# PROC106B_HD_CONN_PWR_SW.net
KiCad netlist of a schematic drawn in Altium Designer
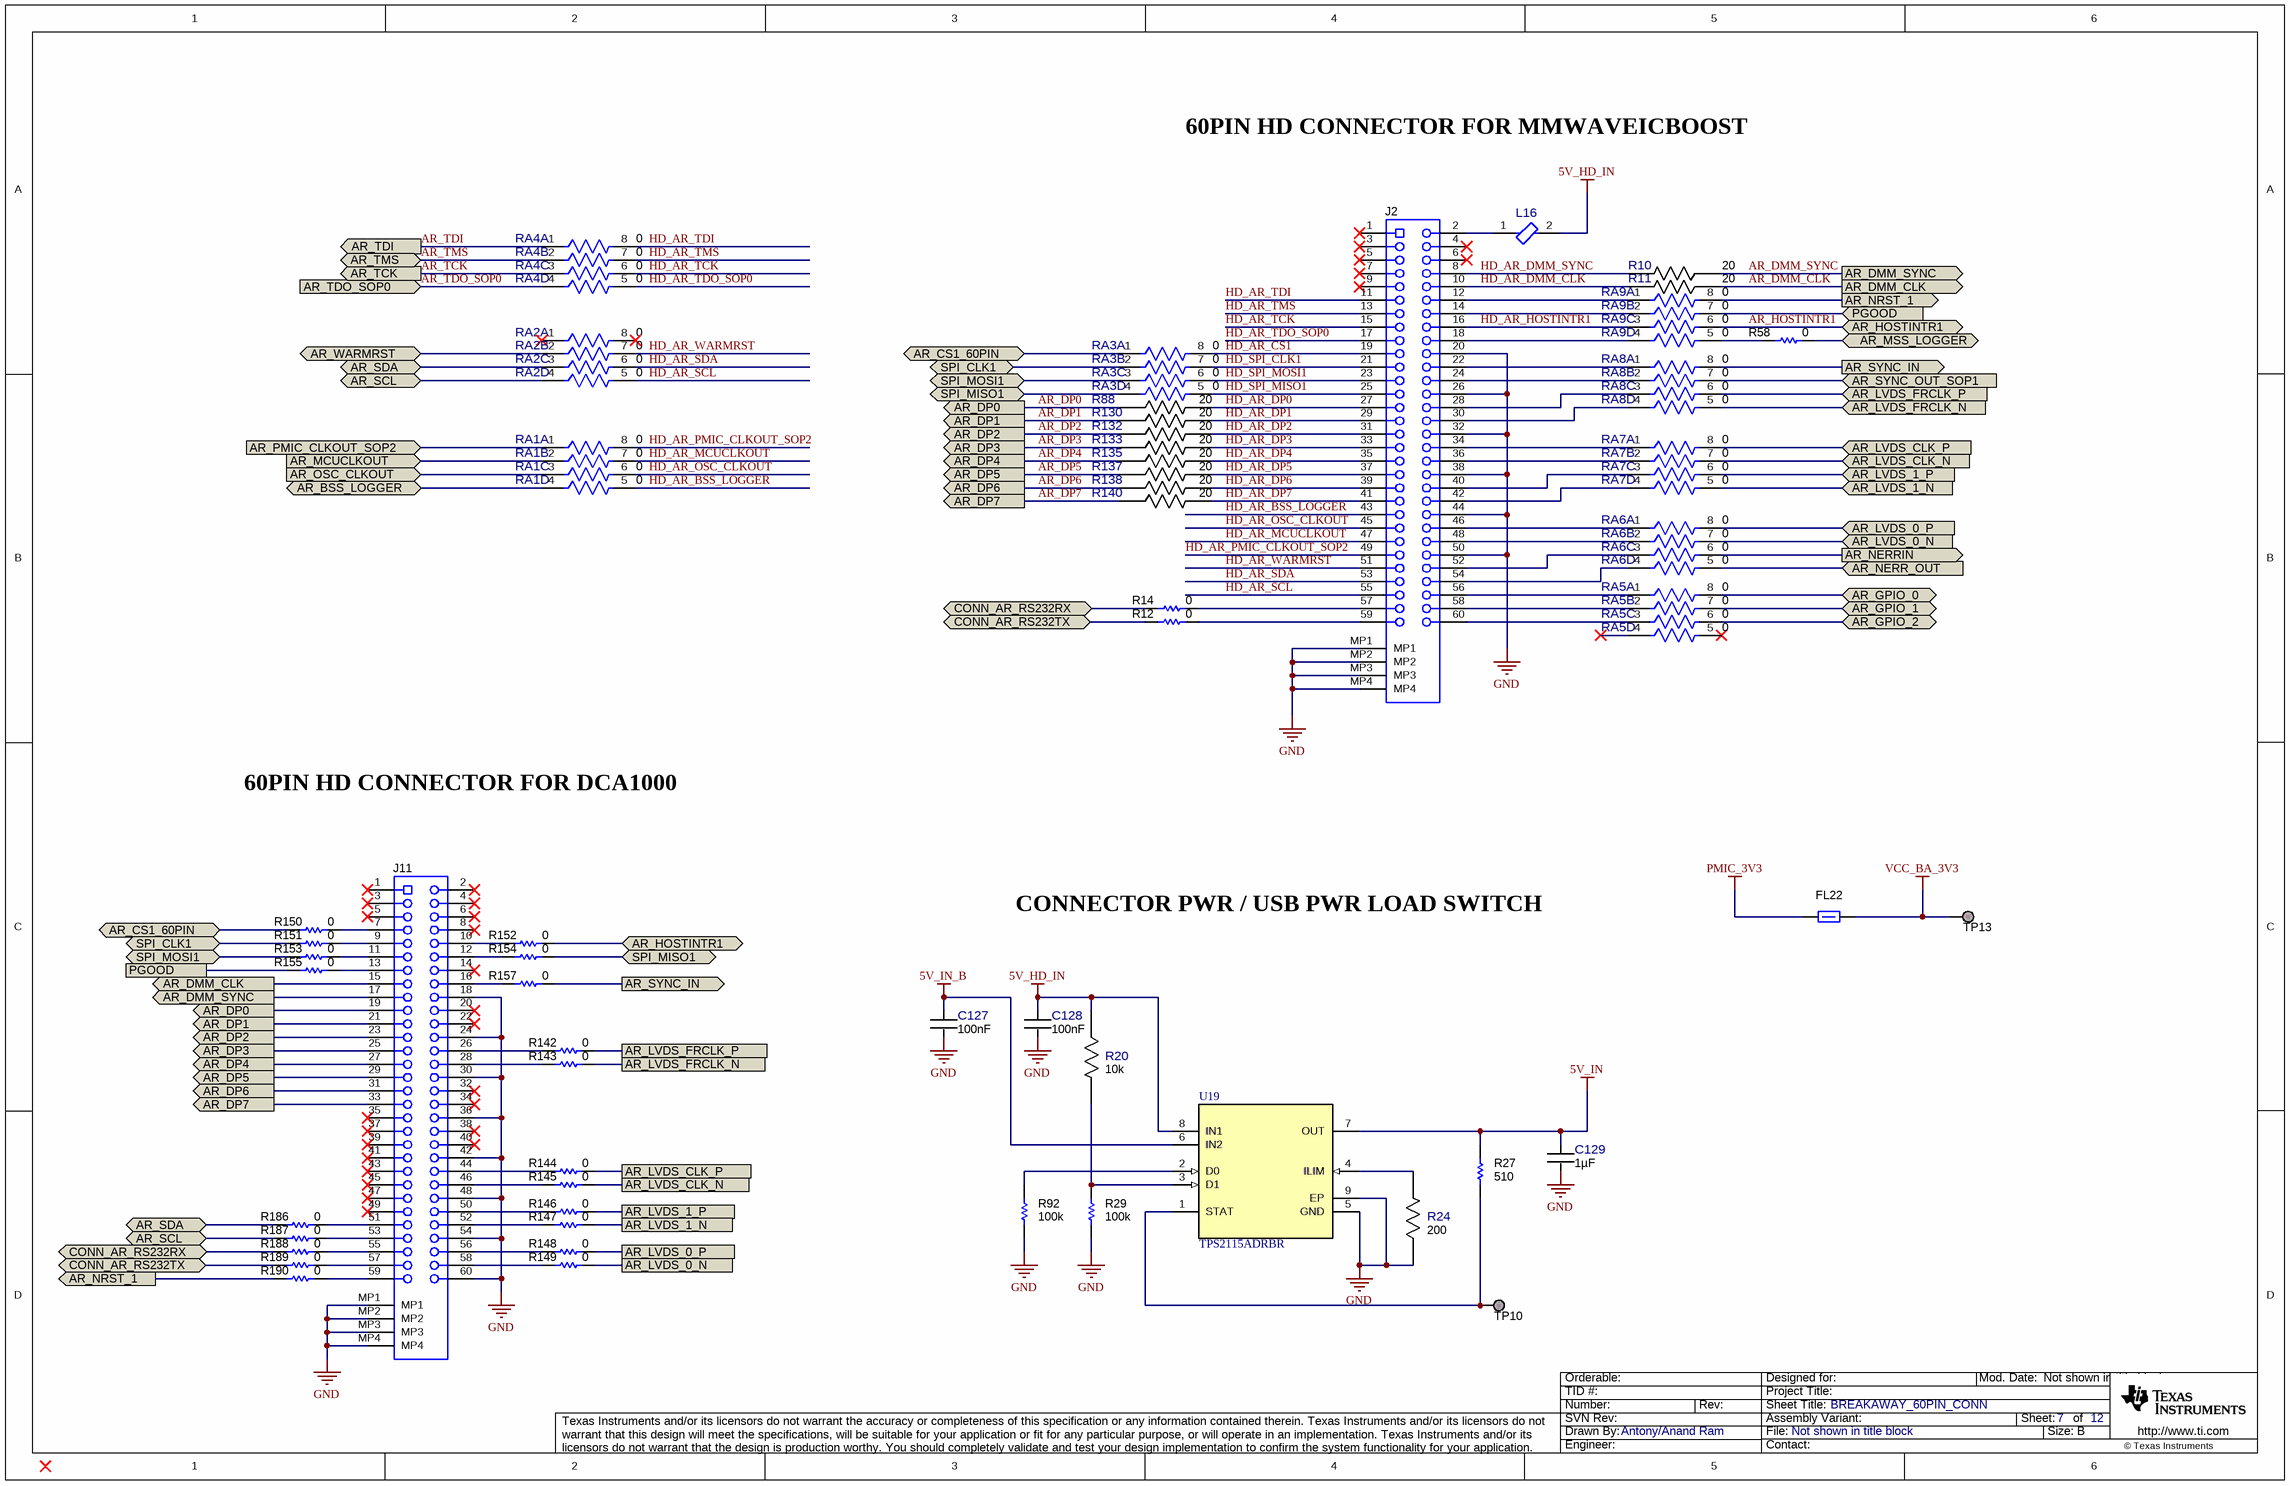
[diagram p0: PROC106B_HD_CONN_PWR_SW.SchDoc]

(export (version "E")
  (design (tool "Eeschema 10.0.6"))
  (components
    (comp (ref "C127")
      (value "GRM033R6YA104KE14D")
      (footprint "FP-GRM033R6YA104KE14D_0201 (0603 Metric)-IPC_C")
      (description "Cap Ceramic 0.1uF 35V X5R 10% Pad SMD 0201 85C T/R")
      (fields (field (name "CAP_F") "100nF") (field (name "MANUFACTURER") "Murata Electronics North America"))
      (libsource (lib "Altium Vault - TI") (part "SYM-B32642B0223J"))
    )
    (comp (ref "C128")
      (value "GRM033R6YA104KE14D")
      (footprint "FP-GRM033R6YA104KE14D_0201 (0603 Metric)-IPC_C")
      (description "Cap Ceramic 0.1uF 35V X5R 10% Pad SMD 0201 85C T/R")
      (fields (field (name "CAP_F") "100nF") (field (name "MANUFACTURER") "Murata Electronics North America"))
      (libsource (lib "Altium Vault - TI") (part "SYM-B32642B0223J"))
    )
    (comp (ref "C129")
      (value "CL03A105MO3NRNH")
      (footprint "FP-CL03A105MO3NRNH_0201-IPC_C")
      (description "1µF ±20% 16V Ceramic Capacitor X5R 0201")
      (fields (field (name "CAP_F") "1µF") (field (name "MANUFACTURER") "Samsung Electro-Mechanics"))
      (libsource (lib "Altium Vault - TI") (part "SYM-B32642B0223J"))
    )
    (comp (ref "FL22")
      (value "BLM15PD300SZ1D")
      (footprint "0402L")
      (description "Inductor, Ferrite Bead, Ferrite, 2.2 A, 0.035 ohm, AEC-Q200 Grade 1, SMD")
      (fields (field (name "MANUFACTURER") "MuRata") (field (name "PUBLISHER") "Texas Instruments"))
      (libsource (lib "Altium Vault - TI") (part "Ferrite_Bead"))
    )
    (comp (ref "J2")
      (value "QSH-030-01-L-D-A")
      (footprint "Samtec_QSH-030-01-X-D-A")
      (description "Receptacle, 0.5 mm, 30x2, Gold, TH")
      (fields (field (name "MANUFACTURER") "Samtec") (field (name "PUBLISHER") "Texas Instruments"))
      (libsource (lib "Altium Vault - TI") (part "Receptacle_30x2_4MP_LeftRight"))
    )
    (comp (ref "J11")
      (value "QSH-030-01-L-D-A")
      (footprint "Samtec_QSH-030-01-X-D-A")
      (description "Receptacle, 0.5 mm, 30x2, Gold, TH")
      (fields (field (name "MANUFACTURER") "Samtec") (field (name "PUBLISHER") "Texas Instruments"))
      (libsource (lib "Altium Vault - TI") (part "CMP-0075524-1"))
    )
    (comp (ref "L16")
      (value "MPZ2012S101ATD25")
      (footprint "FP-MPZ2012S101ATD25_0805-MFG")
      (description "100 Ohms @ 100MHz 1 Power Line Ferrite Bead 0805 (2012 Metric) 4A 20mOhm")
      (fields (field (name "MANUFACTURER") "TDK") (field (name "DIGIKEY PART NUMBER") "445-172903-1-ND"))
      (libsource (lib "Altium Vault - TI") (part "SYM-MPZ2012S101ATD25"))
    )
    (comp (ref "R10")
      (value "AC0201FR-0720RL")
      (footprint "FP-AC0201FR-0720RL_0201-IPC_C")
      (description "RES SMD 20 OHM 1% 1/20W 0201")
      (fields (field (name "MANUFACTURER") "Yageo") (field (name "RES_OHM") "20"))
      (libsource (lib "Altium Vault - TI") (part "SYM-PMR18EZPJ000"))
    )
    (comp (ref "R11")
      (value "AC0201FR-0720RL")
      (footprint "FP-AC0201FR-0720RL_0201-IPC_C")
      (description "RES SMD 20 OHM 1% 1/20W 0201")
      (fields (field (name "MANUFACTURER") "Yageo") (field (name "RES_OHM") "20"))
      (libsource (lib "Altium Vault - TI") (part "SYM-PMR18EZPJ000"))
    )
    (comp (ref "R12")
      (value "RC0201JR-070RL")
      (footprint "FP-RC0201JR-070RL_0201 (0603 Metric)-MFG")
      (description "RES SMD 0 OHM JUMPER 1/20W 0201")
      (fields (field (name "MANUFACTURER") "Yageo") (field (name "RES_OHM") "0"))
      (libsource (lib "Altium Vault - TI") (part "SYM-WSR3R1500F"))
    )
    (comp (ref "R14")
      (value "RC0201JR-070RL")
      (footprint "FP-RC0201JR-070RL_0201 (0603 Metric)-MFG")
      (description "RES SMD 0 OHM JUMPER 1/20W 0201")
      (fields (field (name "MANUFACTURER") "Yageo") (field (name "RES_OHM") "0"))
      (libsource (lib "Altium Vault - TI") (part "SYM-WSR3R1500F"))
    )
    (comp (ref "R20")
      (value "RR0306P-103-D")
      (footprint "FP-RR0306P-103-D_0201-IPC_C")
      (description "10 kOhms ±0.5% 0.05W, 1/20W Chip Resistor 0201 (0603 Metric)  Thin Film")
      (fields (field (name "MANUFACTURER") "Susumu") (field (name "RES_OHM") "10k"))
      (libsource (lib "Altium Vault - TI") (part "SYM-PMR18EZPJ000"))
    )
    (comp (ref "R24")
      (value "CRCW0402200RFKEDHP")
      (footprint "FP-CRCW0402200RFKEDHP_0402-IPC_C")
      (description "RES SMD 200 OHM 1% 1/5W 0402")
      (fields (field (name "MANUFACTURER") "Vishay Dale") (field (name "RES_OHM") "200"))
      (libsource (lib "Altium Vault - TI") (part "SYM-PMR18EZPJ000"))
    )
    (comp (ref "R27")
      (value "510")
      (footprint "0201L")
      (description "RES, 510, 5%, 0.05 W, 0201")
      (fields
        (field (name "MANUFACTURER") "Yageo America")
        (field (name "PARTNUMBER") "RC0201JR-07510RL")
        (field (name "PUBLISHER") "Texas Instruments")
      )
      (libsource (lib "Altium Vault - TI") (part "Resistor"))
    )
    (comp (ref "R29")
      (value "100k")
      (footprint "0201L")
      (description "RES, 100 k, 1%, 0.05 W, 0201")
      (fields (field (name "MANUFACTURER") "Vishay-Dale") (field (name "PARTNUMBER") "CRCW0201100KFKED"))
      (libsource (lib "Altium Vault - TI") (part "Resistor"))
    )
    (comp (ref "R58")
      (value "RC0201JR-070RL")
      (footprint "FP-RC0201JR-070RL_0201 (0603 Metric)-MFG")
      (description "RES SMD 0 OHM JUMPER 1/20W 0201")
      (fields (field (name "MANUFACTURER") "Yageo") (field (name "RES_OHM") "0"))
      (libsource (lib "Altium Vault - TI") (part "SYM-WSR3R1500F"))
    )
    (comp (ref "R88")
      (value "AC0201FR-0720RL")
      (footprint "FP-AC0201FR-0720RL_0201-IPC_C")
      (description "RES SMD 20 OHM 1% 1/20W 0201")
      (fields (field (name "MANUFACTURER") "Yageo") (field (name "RES_OHM") "20"))
      (libsource (lib "Altium Vault - TI") (part "SYM-PMR18EZPJ000"))
    )
    (comp (ref "R92")
      (value "100k")
      (footprint "0201L")
      (description "RES, 100 k, 1%, 0.05 W, 0201")
      (fields (field (name "MANUFACTURER") "Vishay-Dale") (field (name "PARTNUMBER") "CRCW0201100KFKED"))
      (libsource (lib "Altium Vault - TI") (part "Resistor"))
    )
    (comp (ref "R130")
      (value "AC0201FR-0720RL")
      (footprint "FP-AC0201FR-0720RL_0201-IPC_C")
      (description "RES SMD 20 OHM 1% 1/20W 0201")
      (fields (field (name "MANUFACTURER") "Yageo") (field (name "RES_OHM") "20"))
      (libsource (lib "Altium Vault - TI") (part "SYM-PMR18EZPJ000"))
    )
    (comp (ref "R132")
      (value "AC0201FR-0720RL")
      (footprint "FP-AC0201FR-0720RL_0201-IPC_C")
      (description "RES SMD 20 OHM 1% 1/20W 0201")
      (fields (field (name "MANUFACTURER") "Yageo") (field (name "RES_OHM") "20"))
      (libsource (lib "Altium Vault - TI") (part "SYM-PMR18EZPJ000"))
    )
    (comp (ref "R133")
      (value "AC0201FR-0720RL")
      (footprint "FP-AC0201FR-0720RL_0201-IPC_C")
      (description "RES SMD 20 OHM 1% 1/20W 0201")
      (fields (field (name "MANUFACTURER") "Yageo") (field (name "RES_OHM") "20"))
      (libsource (lib "Altium Vault - TI") (part "SYM-PMR18EZPJ000"))
    )
    (comp (ref "R135")
      (value "AC0201FR-0720RL")
      (footprint "FP-AC0201FR-0720RL_0201-IPC_C")
      (description "RES SMD 20 OHM 1% 1/20W 0201")
      (fields (field (name "MANUFACTURER") "Yageo") (field (name "RES_OHM") "20"))
      (libsource (lib "Altium Vault - TI") (part "SYM-PMR18EZPJ000"))
    )
    (comp (ref "R137")
      (value "AC0201FR-0720RL")
      (footprint "FP-AC0201FR-0720RL_0201-IPC_C")
      (description "RES SMD 20 OHM 1% 1/20W 0201")
      (fields (field (name "MANUFACTURER") "Yageo") (field (name "RES_OHM") "20"))
      (libsource (lib "Altium Vault - TI") (part "SYM-PMR18EZPJ000"))
    )
    (comp (ref "R138")
      (value "AC0201FR-0720RL")
      (footprint "FP-AC0201FR-0720RL_0201-IPC_C")
      (description "RES SMD 20 OHM 1% 1/20W 0201")
      (fields (field (name "MANUFACTURER") "Yageo") (field (name "RES_OHM") "20"))
      (libsource (lib "Altium Vault - TI") (part "SYM-PMR18EZPJ000"))
    )
    (comp (ref "R140")
      (value "AC0201FR-0720RL")
      (footprint "FP-AC0201FR-0720RL_0201-IPC_C")
      (description "RES SMD 20 OHM 1% 1/20W 0201")
      (fields (field (name "MANUFACTURER") "Yageo") (field (name "RES_OHM") "20"))
      (libsource (lib "Altium Vault - TI") (part "SYM-PMR18EZPJ000"))
    )
    (comp (ref "R142")
      (value "RC0201JR-070RL")
      (footprint "FP-RC0201JR-070RL_0201 (0603 Metric)-MFG")
      (description "RES SMD 0 OHM JUMPER 1/20W 0201")
      (fields (field (name "MANUFACTURER") "Yageo") (field (name "RES_OHM") "0"))
      (libsource (lib "Altium Vault - TI") (part "SYM-WSR3R1500F"))
    )
    (comp (ref "R143")
      (value "RC0201JR-070RL")
      (footprint "FP-RC0201JR-070RL_0201 (0603 Metric)-MFG")
      (description "RES SMD 0 OHM JUMPER 1/20W 0201")
      (fields (field (name "MANUFACTURER") "Yageo") (field (name "RES_OHM") "0"))
      (libsource (lib "Altium Vault - TI") (part "SYM-WSR3R1500F"))
    )
    (comp (ref "R144")
      (value "RC0201JR-070RL")
      (footprint "FP-RC0201JR-070RL_0201 (0603 Metric)-MFG")
      (description "RES SMD 0 OHM JUMPER 1/20W 0201")
      (fields (field (name "MANUFACTURER") "Yageo") (field (name "RES_OHM") "0"))
      (libsource (lib "Altium Vault - TI") (part "SYM-WSR3R1500F"))
    )
    (comp (ref "R145")
      (value "RC0201JR-070RL")
      (footprint "FP-RC0201JR-070RL_0201 (0603 Metric)-MFG")
      (description "RES SMD 0 OHM JUMPER 1/20W 0201")
      (fields (field (name "MANUFACTURER") "Yageo") (field (name "RES_OHM") "0"))
      (libsource (lib "Altium Vault - TI") (part "SYM-WSR3R1500F"))
    )
    (comp (ref "R146")
      (value "RC0201JR-070RL")
      (footprint "FP-RC0201JR-070RL_0201 (0603 Metric)-MFG")
      (description "RES SMD 0 OHM JUMPER 1/20W 0201")
      (fields (field (name "MANUFACTURER") "Yageo") (field (name "RES_OHM") "0"))
      (libsource (lib "Altium Vault - TI") (part "SYM-WSR3R1500F"))
    )
    (comp (ref "R147")
      (value "RC0201JR-070RL")
      (footprint "FP-RC0201JR-070RL_0201 (0603 Metric)-MFG")
      (description "RES SMD 0 OHM JUMPER 1/20W 0201")
      (fields (field (name "MANUFACTURER") "Yageo") (field (name "RES_OHM") "0"))
      (libsource (lib "Altium Vault - TI") (part "SYM-WSR3R1500F"))
    )
    (comp (ref "R148")
      (value "RC0201JR-070RL")
      (footprint "FP-RC0201JR-070RL_0201 (0603 Metric)-MFG")
      (description "RES SMD 0 OHM JUMPER 1/20W 0201")
      (fields (field (name "MANUFACTURER") "Yageo") (field (name "RES_OHM") "0"))
      (libsource (lib "Altium Vault - TI") (part "SYM-WSR3R1500F"))
    )
    (comp (ref "R149")
      (value "RC0201JR-070RL")
      (footprint "FP-RC0201JR-070RL_0201 (0603 Metric)-MFG")
      (description "RES SMD 0 OHM JUMPER 1/20W 0201")
      (fields (field (name "MANUFACTURER") "Yageo") (field (name "RES_OHM") "0"))
      (libsource (lib "Altium Vault - TI") (part "SYM-WSR3R1500F"))
    )
    (comp (ref "R150")
      (value "RC0201JR-070RL")
      (footprint "FP-RC0201JR-070RL_0201 (0603 Metric)-MFG")
      (description "RES SMD 0 OHM JUMPER 1/20W 0201")
      (fields (field (name "MANUFACTURER") "Yageo") (field (name "RES_OHM") "0"))
      (libsource (lib "Altium Vault - TI") (part "SYM-WSR3R1500F"))
    )
    (comp (ref "R151")
      (value "RC0201JR-070RL")
      (footprint "FP-RC0201JR-070RL_0201 (0603 Metric)-MFG")
      (description "RES SMD 0 OHM JUMPER 1/20W 0201")
      (fields (field (name "MANUFACTURER") "Yageo") (field (name "RES_OHM") "0"))
      (libsource (lib "Altium Vault - TI") (part "SYM-WSR3R1500F"))
    )
    (comp (ref "R152")
      (value "RC0201JR-070RL")
      (footprint "FP-RC0201JR-070RL_0201 (0603 Metric)-MFG")
      (description "RES SMD 0 OHM JUMPER 1/20W 0201")
      (fields (field (name "MANUFACTURER") "Yageo") (field (name "RES_OHM") "0"))
      (libsource (lib "Altium Vault - TI") (part "SYM-WSR3R1500F"))
    )
    (comp (ref "R153")
      (value "RC0201JR-070RL")
      (footprint "FP-RC0201JR-070RL_0201 (0603 Metric)-MFG")
      (description "RES SMD 0 OHM JUMPER 1/20W 0201")
      (fields (field (name "MANUFACTURER") "Yageo") (field (name "RES_OHM") "0"))
      (libsource (lib "Altium Vault - TI") (part "SYM-WSR3R1500F"))
    )
    (comp (ref "R154")
      (value "RC0201JR-070RL")
      (footprint "FP-RC0201JR-070RL_0201 (0603 Metric)-MFG")
      (description "RES SMD 0 OHM JUMPER 1/20W 0201")
      (fields (field (name "MANUFACTURER") "Yageo") (field (name "RES_OHM") "0"))
      (libsource (lib "Altium Vault - TI") (part "SYM-WSR3R1500F"))
    )
    (comp (ref "R155")
      (value "RC0201JR-070RL")
      (footprint "FP-RC0201JR-070RL_0201 (0603 Metric)-MFG")
      (description "RES SMD 0 OHM JUMPER 1/20W 0201")
      (fields (field (name "MANUFACTURER") "Yageo") (field (name "RES_OHM") "0"))
      (libsource (lib "Altium Vault - TI") (part "SYM-WSR3R1500F"))
    )
    (comp (ref "R157")
      (value "RC0201JR-070RL")
      (footprint "FP-RC0201JR-070RL_0201 (0603 Metric)-MFG")
      (description "RES SMD 0 OHM JUMPER 1/20W 0201")
      (fields (field (name "MANUFACTURER") "Yageo") (field (name "RES_OHM") "0"))
      (libsource (lib "Altium Vault - TI") (part "SYM-WSR3R1500F"))
    )
    (comp (ref "R186")
      (value "RC0201JR-070RL")
      (footprint "FP-RC0201JR-070RL_0201 (0603 Metric)-MFG")
      (description "RES SMD 0 OHM JUMPER 1/20W 0201")
      (fields (field (name "MANUFACTURER") "Yageo") (field (name "RES_OHM") "0"))
      (libsource (lib "Altium Vault - TI") (part "SYM-WSR3R1500F"))
    )
    (comp (ref "R187")
      (value "RC0201JR-070RL")
      (footprint "FP-RC0201JR-070RL_0201 (0603 Metric)-MFG")
      (description "RES SMD 0 OHM JUMPER 1/20W 0201")
      (fields (field (name "MANUFACTURER") "Yageo") (field (name "RES_OHM") "0"))
      (libsource (lib "Altium Vault - TI") (part "SYM-WSR3R1500F"))
    )
    (comp (ref "R188")
      (value "RC0201JR-070RL")
      (footprint "FP-RC0201JR-070RL_0201 (0603 Metric)-MFG")
      (description "RES SMD 0 OHM JUMPER 1/20W 0201")
      (fields (field (name "MANUFACTURER") "Yageo") (field (name "RES_OHM") "0"))
      (libsource (lib "Altium Vault - TI") (part "SYM-WSR3R1500F"))
    )
    (comp (ref "R189")
      (value "RC0201JR-070RL")
      (footprint "FP-RC0201JR-070RL_0201 (0603 Metric)-MFG")
      (description "RES SMD 0 OHM JUMPER 1/20W 0201")
      (fields (field (name "MANUFACTURER") "Yageo") (field (name "RES_OHM") "0"))
      (libsource (lib "Altium Vault - TI") (part "SYM-WSR3R1500F"))
    )
    (comp (ref "R190")
      (value "RC0201JR-070RL")
      (footprint "FP-RC0201JR-070RL_0201 (0603 Metric)-MFG")
      (description "RES SMD 0 OHM JUMPER 1/20W 0201")
      (fields (field (name "MANUFACTURER") "Yageo") (field (name "RES_OHM") "0"))
      (libsource (lib "Altium Vault - TI") (part "SYM-WSR3R1500F"))
    )
    (comp (ref "RA1")
      (value "EXB-18VR000X")
      (footprint "FP-EXB-18VR000X_0502-MFG")
      (description "RES ARRAY 4 RES ZERO OHM 0502")
      (fields (field (name "MANUFACTURER") "Panasonic Electronic Components") (field (name "RES_OHM") "0"))
      (libsource (lib "Altium Vault - TI") (part "SYM-EXB-18VR000X"))
    )
    (comp (ref "RA2")
      (value "EXB-18VR000X")
      (footprint "FP-EXB-18VR000X_0502-MFG")
      (description "RES ARRAY 4 RES ZERO OHM 0502")
      (fields (field (name "MANUFACTURER") "Panasonic Electronic Components") (field (name "RES_OHM") "0"))
      (libsource (lib "Altium Vault - TI") (part "SYM-EXB-18VR000X"))
    )
    (comp (ref "RA3")
      (value "EXB-18VR000X")
      (footprint "FP-EXB-18VR000X_0502-MFG")
      (description "RES ARRAY 4 RES ZERO OHM 0502")
      (fields (field (name "MANUFACTURER") "Panasonic Electronic Components") (field (name "RES_OHM") "0"))
      (libsource (lib "Altium Vault - TI") (part "SYM-EXB-18VR000X"))
    )
    (comp (ref "RA4")
      (value "EXB-18VR000X")
      (footprint "FP-EXB-18VR000X_0502-MFG")
      (description "RES ARRAY 4 RES ZERO OHM 0502")
      (fields (field (name "MANUFACTURER") "Panasonic Electronic Components") (field (name "RES_OHM") "0"))
      (libsource (lib "Altium Vault - TI") (part "SYM-EXB-18VR000X"))
    )
    (comp (ref "RA5")
      (value "EXB-18VR000X")
      (footprint "FP-EXB-18VR000X_0502-MFG")
      (description "RES ARRAY 4 RES ZERO OHM 0502")
      (fields (field (name "MANUFACTURER") "Panasonic Electronic Components") (field (name "RES_OHM") "0"))
      (libsource (lib "Altium Vault - TI") (part "SYM-EXB-18VR000X"))
    )
    (comp (ref "RA6")
      (value "EXB-18VR000X")
      (footprint "FP-EXB-18VR000X_0502-MFG")
      (description "RES ARRAY 4 RES ZERO OHM 0502")
      (fields (field (name "MANUFACTURER") "Panasonic Electronic Components") (field (name "RES_OHM") "0"))
      (libsource (lib "Altium Vault - TI") (part "SYM-EXB-18VR000X"))
    )
    (comp (ref "RA7")
      (value "EXB-18VR000X")
      (footprint "FP-EXB-18VR000X_0502-MFG")
      (description "RES ARRAY 4 RES ZERO OHM 0502")
      (fields (field (name "MANUFACTURER") "Panasonic Electronic Components") (field (name "RES_OHM") "0"))
      (libsource (lib "Altium Vault - TI") (part "SYM-EXB-18VR000X"))
    )
    (comp (ref "RA8")
      (value "EXB-18VR000X")
      (footprint "FP-EXB-18VR000X_0502-MFG")
      (description "RES ARRAY 4 RES ZERO OHM 0502")
      (fields (field (name "MANUFACTURER") "Panasonic Electronic Components") (field (name "RES_OHM") "0"))
      (libsource (lib "Altium Vault - TI") (part "SYM-EXB-18VR000X"))
    )
    (comp (ref "RA9")
      (value "EXB-18VR000X")
      (footprint "FP-EXB-18VR000X_0502-MFG")
      (description "RES ARRAY 4 RES ZERO OHM 0502")
      (fields (field (name "MANUFACTURER") "Panasonic Electronic Components") (field (name "RES_OHM") "0"))
      (libsource (lib "Altium Vault - TI") (part "SYM-EXB-18VR000X"))
    )
    (comp (ref "TP10")
      (value "TESTPOINT")
      (footprint "TP_25MIL-SMT")
      (description "TEST POINT.  No entry in BOM.")
      (libsource (lib "Altium Vault - TI") (part "TESTPOINT"))
    )
    (comp (ref "TP13")
      (value "TESTPOINT")
      (footprint "TP_25MIL-SMT")
      (description "TEST POINT.  No entry in BOM.")
      (libsource (lib "Altium Vault - TI") (part "TESTPOINT"))
    )
    (comp (ref "U19")
      (value "TPS2115ADRBR")
      (footprint "DRB0008B")
      (fields (field (name "MANUFACTURER") "Texas Instruments"))
      (libsource (lib "Altium Vault - TI") (part "TI-TPS2115ADRB8-2400X1650TP"))
    )
  )
  (nets
    (net (code "1") (name "/AR_BSS_LOGGER") (class "Default")
      (node (ref "RA1") (pin "4") (pinfunction "4_4") (pintype "passive"))
    )
    (net (code "2") (name "/AR_CS1_60PIN") (class "Default")
      (node (ref "R150") (pin "2") (pinfunction "2_2") (pintype "passive"))
      (node (ref "RA3") (pin "1") (pinfunction "1_1") (pintype "passive"))
    )
    (net (code "3") (name "/AR_DMM_CLK") (class "Default")
      (node (ref "J11") (pin "15") (pinfunction "15_15") (pintype "passive"))
      (node (ref "R11") (pin "1") (pinfunction "1_1") (pintype "passive"))
    )
    (net (code "4") (name "/AR_DMM_SYNC") (class "Default")
      (node (ref "J11") (pin "17") (pinfunction "17_17") (pintype "passive"))
      (node (ref "R10") (pin "1") (pinfunction "1_1") (pintype "passive"))
    )
    (net (code "5") (name "/AR_DP0") (class "Default")
      (node (ref "J11") (pin "19") (pinfunction "19_19") (pintype "passive"))
      (node (ref "R88") (pin "1") (pinfunction "1_1") (pintype "passive"))
    )
    (net (code "6") (name "/AR_DP1") (class "Default")
      (node (ref "J11") (pin "21") (pinfunction "21_21") (pintype "passive"))
      (node (ref "R130") (pin "1") (pinfunction "1_1") (pintype "passive"))
    )
    (net (code "7") (name "/AR_DP2") (class "Default")
      (node (ref "J11") (pin "23") (pinfunction "23_23") (pintype "passive"))
      (node (ref "R132") (pin "1") (pinfunction "1_1") (pintype "passive"))
    )
    (net (code "8") (name "/AR_DP3") (class "Default")
      (node (ref "J11") (pin "25") (pinfunction "25_25") (pintype "passive"))
      (node (ref "R133") (pin "1") (pinfunction "1_1") (pintype "passive"))
    )
    (net (code "9") (name "/AR_DP4") (class "Default")
      (node (ref "J11") (pin "27") (pinfunction "27_27") (pintype "passive"))
      (node (ref "R135") (pin "1") (pinfunction "1_1") (pintype "passive"))
    )
    (net (code "10") (name "/AR_DP5") (class "Default")
      (node (ref "J11") (pin "29") (pinfunction "29_29") (pintype "passive"))
      (node (ref "R137") (pin "1") (pinfunction "1_1") (pintype "passive"))
    )
    (net (code "11") (name "/AR_DP6") (class "Default")
      (node (ref "J11") (pin "31") (pinfunction "31_31") (pintype "passive"))
      (node (ref "R138") (pin "1") (pinfunction "1_1") (pintype "passive"))
    )
    (net (code "12") (name "/AR_DP7") (class "Default")
      (node (ref "J11") (pin "33") (pinfunction "33_33") (pintype "passive"))
      (node (ref "R140") (pin "1") (pinfunction "1_1") (pintype "passive"))
    )
    (net (code "13") (name "/AR_GPIO_0") (class "Default")
      (node (ref "RA5") (pin "8") (pinfunction "8_8") (pintype "passive"))
    )
    (net (code "14") (name "/AR_GPIO_1") (class "Default")
      (node (ref "RA5") (pin "7") (pinfunction "7_7") (pintype "passive"))
    )
    (net (code "15") (name "/AR_GPIO_2") (class "Default")
      (node (ref "RA5") (pin "6") (pinfunction "6_6") (pintype "passive"))
    )
    (net (code "16") (name "/AR_HOSTINTR1") (class "Default")
      (node (ref "R152") (pin "1") (pinfunction "1_1") (pintype "passive"))
      (node (ref "RA9") (pin "6") (pinfunction "6_6") (pintype "passive"))
    )
    (net (code "17") (name "/AR_LVDS_0_N") (class "Default")
      (node (ref "R149") (pin "1") (pinfunction "1_1") (pintype "passive"))
      (node (ref "RA6") (pin "7") (pinfunction "7_7") (pintype "passive"))
    )
    (net (code "18") (name "/AR_LVDS_0_P") (class "Default")
      (node (ref "R148") (pin "1") (pinfunction "1_1") (pintype "passive"))
      (node (ref "RA6") (pin "8") (pinfunction "8_8") (pintype "passive"))
    )
    (net (code "19") (name "/AR_LVDS_1_N") (class "Default")
      (node (ref "R147") (pin "1") (pinfunction "1_1") (pintype "passive"))
      (node (ref "RA7") (pin "5") (pinfunction "5_5") (pintype "passive"))
    )
    (net (code "20") (name "/AR_LVDS_1_P") (class "Default")
      (node (ref "R146") (pin "1") (pinfunction "1_1") (pintype "passive"))
      (node (ref "RA7") (pin "6") (pinfunction "6_6") (pintype "passive"))
    )
    (net (code "21") (name "/AR_LVDS_CLK_N") (class "Default")
      (node (ref "R145") (pin "1") (pinfunction "1_1") (pintype "passive"))
      (node (ref "RA7") (pin "7") (pinfunction "7_7") (pintype "passive"))
    )
    (net (code "22") (name "/AR_LVDS_CLK_P") (class "Default")
      (node (ref "R144") (pin "1") (pinfunction "1_1") (pintype "passive"))
      (node (ref "RA7") (pin "8") (pinfunction "8_8") (pintype "passive"))
    )
    (net (code "23") (name "/AR_LVDS_FRCLK_N") (class "Default")
      (node (ref "R143") (pin "1") (pinfunction "1_1") (pintype "passive"))
      (node (ref "RA8") (pin "5") (pinfunction "5_5") (pintype "passive"))
    )
    (net (code "24") (name "/AR_LVDS_FRCLK_P") (class "Default")
      (node (ref "R142") (pin "1") (pinfunction "1_1") (pintype "passive"))
      (node (ref "RA8") (pin "6") (pinfunction "6_6") (pintype "passive"))
    )
    (net (code "25") (name "/AR_MCUCLKOUT") (class "Default")
      (node (ref "RA1") (pin "2") (pinfunction "2_2") (pintype "passive"))
    )
    (net (code "26") (name "/AR_MSS_LOGGER") (class "Default")
      (node (ref "R58") (pin "1") (pinfunction "1_1") (pintype "passive"))
    )
    (net (code "27") (name "/AR_NERRIN") (class "Default")
      (node (ref "RA6") (pin "6") (pinfunction "6_6") (pintype "passive"))
    )
    (net (code "28") (name "/AR_NERR_OUT") (class "Default")
      (node (ref "RA6") (pin "5") (pinfunction "5_5") (pintype "passive"))
    )
    (net (code "29") (name "/AR_NRST_1") (class "Default")
      (node (ref "R190") (pin "2") (pinfunction "2_2") (pintype "passive"))
      (node (ref "RA9") (pin "8") (pinfunction "8_8") (pintype "passive"))
    )
    (net (code "30") (name "/AR_OSC_CLKOUT") (class "Default")
      (node (ref "RA1") (pin "3") (pinfunction "3_3") (pintype "passive"))
    )
    (net (code "31") (name "/AR_PMIC_CLKOUT_SOP2") (class "Default")
      (node (ref "RA1") (pin "1") (pinfunction "1_1") (pintype "passive"))
    )
    (net (code "32") (name "/AR_SCL") (class "Default")
      (node (ref "R187") (pin "2") (pinfunction "2_2") (pintype "passive"))
      (node (ref "RA2") (pin "4") (pinfunction "4_4") (pintype "passive"))
    )
    (net (code "33") (name "/AR_SDA") (class "Default")
      (node (ref "R186") (pin "2") (pinfunction "2_2") (pintype "passive"))
      (node (ref "RA2") (pin "3") (pinfunction "3_3") (pintype "passive"))
    )
    (net (code "34") (name "/AR_SYNC_IN") (class "Default")
      (node (ref "R157") (pin "1") (pinfunction "1_1") (pintype "passive"))
      (node (ref "RA8") (pin "8") (pinfunction "8_8") (pintype "passive"))
    )
    (net (code "35") (name "/AR_SYNC_OUT_SOP1") (class "Default")
      (node (ref "RA8") (pin "7") (pinfunction "7_7") (pintype "passive"))
    )
    (net (code "36") (name "/AR_TCK") (class "Default")
      (node (ref "RA4") (pin "3") (pinfunction "3_3") (pintype "passive"))
    )
    (net (code "37") (name "/AR_TDI") (class "Default")
      (node (ref "RA4") (pin "1") (pinfunction "1_1") (pintype "passive"))
    )
    (net (code "38") (name "/AR_TDO_SOP0") (class "Default")
      (node (ref "RA4") (pin "4") (pinfunction "4_4") (pintype "passive"))
    )
    (net (code "39") (name "/AR_TMS") (class "Default")
      (node (ref "RA4") (pin "2") (pinfunction "2_2") (pintype "passive"))
    )
    (net (code "40") (name "/AR_WARMRST") (class "Default")
      (node (ref "RA2") (pin "2") (pinfunction "2_2") (pintype "passive"))
    )
    (net (code "41") (name "/CONN_AR_RS232RX") (class "Default")
      (node (ref "R14") (pin "2") (pinfunction "2_2") (pintype "passive"))
      (node (ref "R188") (pin "2") (pinfunction "2_2") (pintype "passive"))
    )
    (net (code "42") (name "/CONN_AR_RS232TX") (class "Default")
      (node (ref "R12") (pin "2") (pinfunction "2_2") (pintype "passive"))
      (node (ref "R189") (pin "2") (pinfunction "2_2") (pintype "passive"))
    )
    (net (code "43") (name "/HD_AR_BSS_LOGGER") (class "Default")
      (node (ref "J2") (pin "43") (pinfunction "43_43") (pintype "passive"))
      (node (ref "RA1") (pin "5") (pinfunction "5_5") (pintype "passive"))
    )
    (net (code "44") (name "/HD_AR_CS1") (class "Default")
      (node (ref "J2") (pin "19") (pinfunction "19_19") (pintype "passive"))
      (node (ref "RA3") (pin "8") (pinfunction "8_8") (pintype "passive"))
    )
    (net (code "45") (name "/HD_AR_DMM_CLK") (class "Default")
      (node (ref "J2") (pin "10") (pinfunction "10_10") (pintype "passive"))
      (node (ref "R11") (pin "2") (pinfunction "2_2") (pintype "passive"))
    )
    (net (code "46") (name "/HD_AR_DMM_SYNC") (class "Default")
      (node (ref "J2") (pin "8") (pinfunction "8_8") (pintype "passive"))
      (node (ref "R10") (pin "2") (pinfunction "2_2") (pintype "passive"))
    )
    (net (code "47") (name "/HD_AR_DP0") (class "Default")
      (node (ref "J2") (pin "27") (pinfunction "27_27") (pintype "passive"))
      (node (ref "R88") (pin "2") (pinfunction "2_2") (pintype "passive"))
    )
    (net (code "48") (name "/HD_AR_DP1") (class "Default")
      (node (ref "J2") (pin "29") (pinfunction "29_29") (pintype "passive"))
      (node (ref "R130") (pin "2") (pinfunction "2_2") (pintype "passive"))
    )
    (net (code "49") (name "/HD_AR_DP2") (class "Default")
      (node (ref "J2") (pin "31") (pinfunction "31_31") (pintype "passive"))
      (node (ref "R132") (pin "2") (pinfunction "2_2") (pintype "passive"))
    )
    (net (code "50") (name "/HD_AR_DP3") (class "Default")
      (node (ref "J2") (pin "33") (pinfunction "33_33") (pintype "passive"))
      (node (ref "R133") (pin "2") (pinfunction "2_2") (pintype "passive"))
    )
    (net (code "51") (name "/HD_AR_DP4") (class "Default")
      (node (ref "J2") (pin "35") (pinfunction "35_35") (pintype "passive"))
      (node (ref "R135") (pin "2") (pinfunction "2_2") (pintype "passive"))
    )
    (net (code "52") (name "/HD_AR_DP5") (class "Default")
      (node (ref "J2") (pin "37") (pinfunction "37_37") (pintype "passive"))
      (node (ref "R137") (pin "2") (pinfunction "2_2") (pintype "passive"))
    )
    (net (code "53") (name "/HD_AR_DP6") (class "Default")
      (node (ref "J2") (pin "39") (pinfunction "39_39") (pintype "passive"))
      (node (ref "R138") (pin "2") (pinfunction "2_2") (pintype "passive"))
    )
    (net (code "54") (name "/HD_AR_DP7") (class "Default")
      (node (ref "J2") (pin "41") (pinfunction "41_41") (pintype "passive"))
      (node (ref "R140") (pin "2") (pinfunction "2_2") (pintype "passive"))
    )
    (net (code "55") (name "/HD_AR_HOSTINTR1") (class "Default")
      (node (ref "J2") (pin "16") (pinfunction "16_16") (pintype "passive"))
      (node (ref "RA9") (pin "3") (pinfunction "3_3") (pintype "passive"))
    )
    (net (code "56") (name "/HD_AR_MCUCLKOUT") (class "Default")
      (node (ref "J2") (pin "47") (pinfunction "47_47") (pintype "passive"))
      (node (ref "RA1") (pin "7") (pinfunction "7_7") (pintype "passive"))
    )
    (net (code "57") (name "/HD_AR_OSC_CLKOUT") (class "Default")
      (node (ref "J2") (pin "45") (pinfunction "45_45") (pintype "passive"))
      (node (ref "RA1") (pin "6") (pinfunction "6_6") (pintype "passive"))
    )
    (net (code "58") (name "/HD_AR_PMIC_CLKOUT_SOP2") (class "Default")
      (node (ref "J2") (pin "49") (pinfunction "49_49") (pintype "passive"))
      (node (ref "RA1") (pin "8") (pinfunction "8_8") (pintype "passive"))
    )
    (net (code "59") (name "/HD_AR_SCL") (class "Default")
      (node (ref "J2") (pin "55") (pinfunction "55_55") (pintype "passive"))
      (node (ref "RA2") (pin "5") (pinfunction "5_5") (pintype "passive"))
    )
    (net (code "60") (name "/HD_AR_SDA") (class "Default")
      (node (ref "J2") (pin "53") (pinfunction "53_53") (pintype "passive"))
      (node (ref "RA2") (pin "6") (pinfunction "6_6") (pintype "passive"))
    )
    (net (code "61") (name "/HD_AR_TCK") (class "Default")
      (node (ref "J2") (pin "15") (pinfunction "15_15") (pintype "passive"))
      (node (ref "RA4") (pin "6") (pinfunction "6_6") (pintype "passive"))
    )
    (net (code "62") (name "/HD_AR_TDI") (class "Default")
      (node (ref "J2") (pin "11") (pinfunction "11_11") (pintype "passive"))
      (node (ref "RA4") (pin "8") (pinfunction "8_8") (pintype "passive"))
    )
    (net (code "63") (name "/HD_AR_TDO_SOP0") (class "Default")
      (node (ref "J2") (pin "17") (pinfunction "17_17") (pintype "passive"))
      (node (ref "RA4") (pin "5") (pinfunction "5_5") (pintype "passive"))
    )
    (net (code "64") (name "/HD_AR_TMS") (class "Default")
      (node (ref "J2") (pin "13") (pinfunction "13_13") (pintype "passive"))
      (node (ref "RA4") (pin "7") (pinfunction "7_7") (pintype "passive"))
    )
    (net (code "65") (name "/HD_AR_WARMRST") (class "Default")
      (node (ref "J2") (pin "51") (pinfunction "51_51") (pintype "passive"))
      (node (ref "RA2") (pin "7") (pinfunction "7_7") (pintype "passive"))
    )
    (net (code "66") (name "/HD_SPI_CLK1") (class "Default")
      (node (ref "J2") (pin "21") (pinfunction "21_21") (pintype "passive"))
      (node (ref "RA3") (pin "7") (pinfunction "7_7") (pintype "passive"))
    )
    (net (code "67") (name "/HD_SPI_MISO1") (class "Default")
      (node (ref "J2") (pin "25") (pinfunction "25_25") (pintype "passive"))
      (node (ref "RA3") (pin "5") (pinfunction "5_5") (pintype "passive"))
    )
    (net (code "68") (name "/HD_SPI_MOSI1") (class "Default")
      (node (ref "J2") (pin "23") (pinfunction "23_23") (pintype "passive"))
      (node (ref "RA3") (pin "6") (pinfunction "6_6") (pintype "passive"))
    )
    (net (code "69") (name "/PGOOD") (class "Default")
      (node (ref "R155") (pin "2") (pinfunction "2_2") (pintype "passive"))
      (node (ref "RA9") (pin "7") (pinfunction "7_7") (pintype "passive"))
    )
    (net (code "70") (name "/SPI_CLK1") (class "Default")
      (node (ref "R151") (pin "2") (pinfunction "2_2") (pintype "passive"))
      (node (ref "RA3") (pin "2") (pinfunction "2_2") (pintype "passive"))
    )
    (net (code "71") (name "/SPI_MISO1") (class "Default")
      (node (ref "R154") (pin "1") (pinfunction "1_1") (pintype "passive"))
      (node (ref "RA3") (pin "4") (pinfunction "4_4") (pintype "passive"))
    )
    (net (code "72") (name "/SPI_MOSI1") (class "Default")
      (node (ref "R153") (pin "2") (pinfunction "2_2") (pintype "passive"))
      (node (ref "RA3") (pin "3") (pinfunction "3_3") (pintype "passive"))
    )
    (net (code "73") (name "5V_HD_IN") (class "Default")
      (node (ref "C128") (pin "1") (pinfunction "1_1") (pintype "passive"))
      (node (ref "L16") (pin "2") (pinfunction "2_2") (pintype "passive"))
      (node (ref "R20") (pin "1") (pinfunction "1_1") (pintype "passive"))
      (node (ref "U19") (pin "8") (pinfunction "IN1_8") (pintype "power_in"))
    )
    (net (code "74") (name "5V_IN") (class "Default")
      (node (ref "C129") (pin "1") (pinfunction "1_1") (pintype "passive"))
      (node (ref "R27") (pin "1") (pinfunction "1_1") (pintype "passive"))
      (node (ref "U19") (pin "7") (pinfunction "OUT_7") (pintype "power_in"))
    )
    (net (code "75") (name "5V_IN_B") (class "Default")
      (node (ref "C127") (pin "1") (pinfunction "1_1") (pintype "passive"))
      (node (ref "U19") (pin "6") (pinfunction "IN2_6") (pintype "power_in"))
    )
    (net (code "76") (name "GND") (class "Default")
      (node (ref "C127") (pin "2") (pinfunction "2_2") (pintype "passive"))
      (node (ref "C128") (pin "2") (pinfunction "2_2") (pintype "passive"))
      (node (ref "C129") (pin "2") (pinfunction "2_2") (pintype "passive"))
      (node (ref "J11") (pin "18") (pinfunction "18_18") (pintype "passive"))
      (node (ref "J11") (pin "24") (pinfunction "24_24") (pintype "passive"))
      (node (ref "J11") (pin "30") (pinfunction "30_30") (pintype "passive"))
      (node (ref "J11") (pin "36") (pinfunction "36_36") (pintype "passive"))
      (node (ref "J11") (pin "42") (pinfunction "42_42") (pintype "passive"))
      (node (ref "J11") (pin "48") (pinfunction "48_48") (pintype "passive"))
      (node (ref "J11") (pin "54") (pinfunction "54_54") (pintype "passive"))
      (node (ref "J11") (pin "60") (pinfunction "60_60") (pintype "passive"))
      (node (ref "J11") (pin "MP1") (pinfunction "MP1_MP1") (pintype "passive"))
      (node (ref "J11") (pin "MP2") (pinfunction "MP2_MP2") (pintype "passive"))
      (node (ref "J11") (pin "MP3") (pinfunction "MP3_MP3") (pintype "passive"))
      (node (ref "J11") (pin "MP4") (pinfunction "MP4_MP4") (pintype "passive"))
      (node (ref "J2") (pin "20") (pinfunction "20_20") (pintype "passive"))
      (node (ref "J2") (pin "26") (pinfunction "26_26") (pintype "passive"))
      (node (ref "J2") (pin "32") (pinfunction "32_32") (pintype "passive"))
      (node (ref "J2") (pin "38") (pinfunction "38_38") (pintype "passive"))
      (node (ref "J2") (pin "44") (pinfunction "44_44") (pintype "passive"))
      (node (ref "J2") (pin "50") (pinfunction "50_50") (pintype "passive"))
      (node (ref "J2") (pin "MP1") (pinfunction "MP1_MP1") (pintype "passive"))
      (node (ref "J2") (pin "MP2") (pinfunction "MP2_MP2") (pintype "passive"))
      (node (ref "J2") (pin "MP3") (pinfunction "MP3_MP3") (pintype "passive"))
      (node (ref "J2") (pin "MP4") (pinfunction "MP4_MP4") (pintype "passive"))
      (node (ref "R24") (pin "1") (pinfunction "1_1") (pintype "passive"))
      (node (ref "R29") (pin "1") (pinfunction "1_1") (pintype "passive"))
      (node (ref "R92") (pin "2") (pinfunction "2_2") (pintype "passive"))
      (node (ref "U19") (pin "5") (pinfunction "GND_5") (pintype "power_in"))
      (node (ref "U19") (pin "9") (pinfunction "EP_9") (pintype "power_in"))
    )
    (net (code "77") (name "Net-(J2-Pad2)") (class "Default")
      (node (ref "J2") (pin "2") (pinfunction "2_2") (pintype "passive"))
      (node (ref "L16") (pin "1") (pinfunction "1_1") (pintype "passive"))
    )
    (net (code "78") (name "Net-(J2-Pad12)") (class "Default")
      (node (ref "J2") (pin "12") (pinfunction "12_12") (pintype "passive"))
      (node (ref "RA9") (pin "1") (pinfunction "1_1") (pintype "passive"))
    )
    (net (code "79") (name "Net-(J2-Pad14)") (class "Default")
      (node (ref "J2") (pin "14") (pinfunction "14_14") (pintype "passive"))
      (node (ref "RA9") (pin "2") (pinfunction "2_2") (pintype "passive"))
    )
    (net (code "80") (name "Net-(J2-Pad18)") (class "Default")
      (node (ref "J2") (pin "18") (pinfunction "18_18") (pintype "passive"))
      (node (ref "RA9") (pin "4") (pinfunction "4_4") (pintype "passive"))
    )
    (net (code "81") (name "Net-(J2-Pad22)") (class "Default")
      (node (ref "J2") (pin "22") (pinfunction "22_22") (pintype "passive"))
      (node (ref "RA8") (pin "1") (pinfunction "1_1") (pintype "passive"))
    )
    (net (code "82") (name "Net-(J2-Pad24)") (class "Default")
      (node (ref "J2") (pin "24") (pinfunction "24_24") (pintype "passive"))
      (node (ref "RA8") (pin "2") (pinfunction "2_2") (pintype "passive"))
    )
    (net (code "83") (name "Net-(J2-Pad28)") (class "Default")
      (node (ref "J2") (pin "28") (pinfunction "28_28") (pintype "passive"))
      (node (ref "RA8") (pin "3") (pinfunction "3_3") (pintype "passive"))
    )
    (net (code "84") (name "Net-(J2-Pad30)") (class "Default")
      (node (ref "J2") (pin "30") (pinfunction "30_30") (pintype "passive"))
      (node (ref "RA8") (pin "4") (pinfunction "4_4") (pintype "passive"))
    )
    (net (code "85") (name "Net-(J2-Pad34)") (class "Default")
      (node (ref "J2") (pin "34") (pinfunction "34_34") (pintype "passive"))
      (node (ref "RA7") (pin "1") (pinfunction "1_1") (pintype "passive"))
    )
    (net (code "86") (name "Net-(J2-Pad36)") (class "Default")
      (node (ref "J2") (pin "36") (pinfunction "36_36") (pintype "passive"))
      (node (ref "RA7") (pin "2") (pinfunction "2_2") (pintype "passive"))
    )
    (net (code "87") (name "Net-(J2-Pad40)") (class "Default")
      (node (ref "J2") (pin "40") (pinfunction "40_40") (pintype "passive"))
      (node (ref "RA7") (pin "3") (pinfunction "3_3") (pintype "passive"))
    )
    (net (code "88") (name "Net-(J2-Pad42)") (class "Default")
      (node (ref "J2") (pin "42") (pinfunction "42_42") (pintype "passive"))
      (node (ref "RA7") (pin "4") (pinfunction "4_4") (pintype "passive"))
    )
    (net (code "89") (name "Net-(J2-Pad46)") (class "Default")
      (node (ref "J2") (pin "46") (pinfunction "46_46") (pintype "passive"))
      (node (ref "RA6") (pin "1") (pinfunction "1_1") (pintype "passive"))
    )
    (net (code "90") (name "Net-(J2-Pad48)") (class "Default")
      (node (ref "J2") (pin "48") (pinfunction "48_48") (pintype "passive"))
      (node (ref "RA6") (pin "2") (pinfunction "2_2") (pintype "passive"))
    )
    (net (code "91") (name "Net-(J2-Pad52)") (class "Default")
      (node (ref "J2") (pin "52") (pinfunction "52_52") (pintype "passive"))
      (node (ref "RA6") (pin "3") (pinfunction "3_3") (pintype "passive"))
    )
    (net (code "92") (name "Net-(J2-Pad54)") (class "Default")
      (node (ref "J2") (pin "54") (pinfunction "54_54") (pintype "passive"))
      (node (ref "RA6") (pin "4") (pinfunction "4_4") (pintype "passive"))
    )
    (net (code "93") (name "Net-(J2-Pad56)") (class "Default")
      (node (ref "J2") (pin "56") (pinfunction "56_56") (pintype "passive"))
      (node (ref "RA5") (pin "1") (pinfunction "1_1") (pintype "passive"))
    )
    (net (code "94") (name "Net-(J2-Pad57)") (class "Default")
      (node (ref "J2") (pin "57") (pinfunction "57_57") (pintype "passive"))
      (node (ref "R14") (pin "1") (pinfunction "1_1") (pintype "passive"))
    )
    (net (code "95") (name "Net-(J2-Pad58)") (class "Default")
      (node (ref "J2") (pin "58") (pinfunction "58_58") (pintype "passive"))
      (node (ref "RA5") (pin "2") (pinfunction "2_2") (pintype "passive"))
    )
    (net (code "96") (name "Net-(J2-Pad59)") (class "Default")
      (node (ref "J2") (pin "59") (pinfunction "59_59") (pintype "passive"))
      (node (ref "R12") (pin "1") (pinfunction "1_1") (pintype "passive"))
    )
    (net (code "97") (name "Net-(J2-Pad60)") (class "Default")
      (node (ref "J2") (pin "60") (pinfunction "60_60") (pintype "passive"))
      (node (ref "RA5") (pin "3") (pinfunction "3_3") (pintype "passive"))
    )
    (net (code "98") (name "Net-(J11-Pad7)") (class "Default")
      (node (ref "J11") (pin "7") (pinfunction "7_7") (pintype "passive"))
      (node (ref "R150") (pin "1") (pinfunction "1_1") (pintype "passive"))
    )
    (net (code "99") (name "Net-(J11-Pad9)") (class "Default")
      (node (ref "J11") (pin "9") (pinfunction "9_9") (pintype "passive"))
      (node (ref "R151") (pin "1") (pinfunction "1_1") (pintype "passive"))
    )
    (net (code "100") (name "Net-(J11-Pad10)") (class "Default")
      (node (ref "J11") (pin "10") (pinfunction "10_10") (pintype "passive"))
      (node (ref "R152") (pin "2") (pinfunction "2_2") (pintype "passive"))
    )
    (net (code "101") (name "Net-(J11-Pad11)") (class "Default")
      (node (ref "J11") (pin "11") (pinfunction "11_11") (pintype "passive"))
      (node (ref "R153") (pin "1") (pinfunction "1_1") (pintype "passive"))
    )
    (net (code "102") (name "Net-(J11-Pad12)") (class "Default")
      (node (ref "J11") (pin "12") (pinfunction "12_12") (pintype "passive"))
      (node (ref "R154") (pin "2") (pinfunction "2_2") (pintype "passive"))
    )
    (net (code "103") (name "Net-(J11-Pad13)") (class "Default")
      (node (ref "J11") (pin "13") (pinfunction "13_13") (pintype "passive"))
      (node (ref "R155") (pin "1") (pinfunction "1_1") (pintype "passive"))
    )
    (net (code "104") (name "Net-(J11-Pad16)") (class "Default")
      (node (ref "J11") (pin "16") (pinfunction "16_16") (pintype "passive"))
      (node (ref "R157") (pin "2") (pinfunction "2_2") (pintype "passive"))
    )
    (net (code "105") (name "Net-(J11-Pad26)") (class "Default")
      (node (ref "J11") (pin "26") (pinfunction "26_26") (pintype "passive"))
      (node (ref "R142") (pin "2") (pinfunction "2_2") (pintype "passive"))
    )
    (net (code "106") (name "Net-(J11-Pad28)") (class "Default")
      (node (ref "J11") (pin "28") (pinfunction "28_28") (pintype "passive"))
      (node (ref "R143") (pin "2") (pinfunction "2_2") (pintype "passive"))
    )
    (net (code "107") (name "Net-(J11-Pad44)") (class "Default")
      (node (ref "J11") (pin "44") (pinfunction "44_44") (pintype "passive"))
      (node (ref "R144") (pin "2") (pinfunction "2_2") (pintype "passive"))
    )
    (net (code "108") (name "Net-(J11-Pad46)") (class "Default")
      (node (ref "J11") (pin "46") (pinfunction "46_46") (pintype "passive"))
      (node (ref "R145") (pin "2") (pinfunction "2_2") (pintype "passive"))
    )
    (net (code "109") (name "Net-(J11-Pad50)") (class "Default")
      (node (ref "J11") (pin "50") (pinfunction "50_50") (pintype "passive"))
      (node (ref "R146") (pin "2") (pinfunction "2_2") (pintype "passive"))
    )
    (net (code "110") (name "Net-(J11-Pad51)") (class "Default")
      (node (ref "J11") (pin "51") (pinfunction "51_51") (pintype "passive"))
      (node (ref "R186") (pin "1") (pinfunction "1_1") (pintype "passive"))
    )
    (net (code "111") (name "Net-(J11-Pad52)") (class "Default")
      (node (ref "J11") (pin "52") (pinfunction "52_52") (pintype "passive"))
      (node (ref "R147") (pin "2") (pinfunction "2_2") (pintype "passive"))
    )
    (net (code "112") (name "Net-(J11-Pad53)") (class "Default")
      (node (ref "J11") (pin "53") (pinfunction "53_53") (pintype "passive"))
      (node (ref "R187") (pin "1") (pinfunction "1_1") (pintype "passive"))
    )
    (net (code "113") (name "Net-(J11-Pad55)") (class "Default")
      (node (ref "J11") (pin "55") (pinfunction "55_55") (pintype "passive"))
      (node (ref "R188") (pin "1") (pinfunction "1_1") (pintype "passive"))
    )
    (net (code "114") (name "Net-(J11-Pad56)") (class "Default")
      (node (ref "J11") (pin "56") (pinfunction "56_56") (pintype "passive"))
      (node (ref "R148") (pin "2") (pinfunction "2_2") (pintype "passive"))
    )
    (net (code "115") (name "Net-(J11-Pad57)") (class "Default")
      (node (ref "J11") (pin "57") (pinfunction "57_57") (pintype "passive"))
      (node (ref "R189") (pin "1") (pinfunction "1_1") (pintype "passive"))
    )
    (net (code "116") (name "Net-(J11-Pad58)") (class "Default")
      (node (ref "J11") (pin "58") (pinfunction "58_58") (pintype "passive"))
      (node (ref "R149") (pin "2") (pinfunction "2_2") (pintype "passive"))
    )
    (net (code "117") (name "Net-(J11-Pad59)") (class "Default")
      (node (ref "J11") (pin "59") (pinfunction "59_59") (pintype "passive"))
      (node (ref "R190") (pin "1") (pinfunction "1_1") (pintype "passive"))
    )
    (net (code "118") (name "Net-(R58-Pad2)") (class "Default")
      (node (ref "R58") (pin "2") (pinfunction "2_2") (pintype "passive"))
      (node (ref "RA9") (pin "5") (pinfunction "5_5") (pintype "passive"))
    )
    (net (code "119") (name "Net-(U19-D0)") (class "Default")
      (node (ref "R92") (pin "1") (pinfunction "1_1") (pintype "passive"))
      (node (ref "U19") (pin "2") (pinfunction "D0_2") (pintype "input"))
    )
    (net (code "120") (name "Net-(U19-D1)") (class "Default")
      (node (ref "R20") (pin "2") (pinfunction "2_2") (pintype "passive"))
      (node (ref "R29") (pin "2") (pinfunction "2_2") (pintype "passive"))
      (node (ref "U19") (pin "3") (pinfunction "D1_3") (pintype "input"))
    )
    (net (code "121") (name "Net-(U19-ILIM)") (class "Default")
      (node (ref "R24") (pin "2") (pinfunction "2_2") (pintype "passive"))
      (node (ref "U19") (pin "4") (pinfunction "ILIM_4") (pintype "input"))
    )
    (net (code "122") (name "Net-(U19-STAT)") (class "Default")
      (node (ref "R27") (pin "2") (pinfunction "2_2") (pintype "passive"))
      (node (ref "TP10") (pin "1") (pintype "passive"))
      (node (ref "U19") (pin "1") (pinfunction "STAT_1") (pintype "tri_state"))
    )
    (net (code "123") (name "PMIC_3V3") (class "Default")
      (node (ref "FL22") (pin "1") (pinfunction "1_1") (pintype "passive"))
    )
    (net (code "124") (name "VCC_BA_3V3") (class "Default")
      (node (ref "FL22") (pin "2") (pinfunction "2_2") (pintype "passive"))
      (node (ref "TP13") (pin "1") (pintype "passive"))
    )
    (net (code "125") (name "unconnected-(J2-Pad1)") (class "Default")
      (node (ref "J2") (pin "1") (pinfunction "1_1") (pintype "passive+no_connect"))
    )
    (net (code "126") (name "unconnected-(J2-Pad3)") (class "Default")
      (node (ref "J2") (pin "3") (pinfunction "3_3") (pintype "passive+no_connect"))
    )
    (net (code "127") (name "unconnected-(J2-Pad4)") (class "Default")
      (node (ref "J2") (pin "4") (pinfunction "4_4") (pintype "passive+no_connect"))
    )
    (net (code "128") (name "unconnected-(J2-Pad5)") (class "Default")
      (node (ref "J2") (pin "5") (pinfunction "5_5") (pintype "passive+no_connect"))
    )
    (net (code "129") (name "unconnected-(J2-Pad6)") (class "Default")
      (node (ref "J2") (pin "6") (pinfunction "6_6") (pintype "passive+no_connect"))
    )
    (net (code "130") (name "unconnected-(J2-Pad7)") (class "Default")
      (node (ref "J2") (pin "7") (pinfunction "7_7") (pintype "passive+no_connect"))
    )
    (net (code "131") (name "unconnected-(J2-Pad9)") (class "Default")
      (node (ref "J2") (pin "9") (pinfunction "9_9") (pintype "passive+no_connect"))
    )
    (net (code "132") (name "unconnected-(J11-Pad1)") (class "Default")
      (node (ref "J11") (pin "1") (pinfunction "1_1") (pintype "passive+no_connect"))
    )
    (net (code "133") (name "unconnected-(J11-Pad2)") (class "Default")
      (node (ref "J11") (pin "2") (pinfunction "2_2") (pintype "passive+no_connect"))
    )
    (net (code "134") (name "unconnected-(J11-Pad3)") (class "Default")
      (node (ref "J11") (pin "3") (pinfunction "3_3") (pintype "passive+no_connect"))
    )
    (net (code "135") (name "unconnected-(J11-Pad4)") (class "Default")
      (node (ref "J11") (pin "4") (pinfunction "4_4") (pintype "passive+no_connect"))
    )
    (net (code "136") (name "unconnected-(J11-Pad5)") (class "Default")
      (node (ref "J11") (pin "5") (pinfunction "5_5") (pintype "passive+no_connect"))
    )
    (net (code "137") (name "unconnected-(J11-Pad6)") (class "Default")
      (node (ref "J11") (pin "6") (pinfunction "6_6") (pintype "passive+no_connect"))
    )
    (net (code "138") (name "unconnected-(J11-Pad8)") (class "Default")
      (node (ref "J11") (pin "8") (pinfunction "8_8") (pintype "passive+no_connect"))
    )
    (net (code "139") (name "unconnected-(J11-Pad14)") (class "Default")
      (node (ref "J11") (pin "14") (pinfunction "14_14") (pintype "passive+no_connect"))
    )
    (net (code "140") (name "unconnected-(J11-Pad20)") (class "Default")
      (node (ref "J11") (pin "20") (pinfunction "20_20") (pintype "passive+no_connect"))
    )
    (net (code "141") (name "unconnected-(J11-Pad22)") (class "Default")
      (node (ref "J11") (pin "22") (pinfunction "22_22") (pintype "passive+no_connect"))
    )
    (net (code "142") (name "unconnected-(J11-Pad32)") (class "Default")
      (node (ref "J11") (pin "32") (pinfunction "32_32") (pintype "passive+no_connect"))
    )
    (net (code "143") (name "unconnected-(J11-Pad34)") (class "Default")
      (node (ref "J11") (pin "34") (pinfunction "34_34") (pintype "passive+no_connect"))
    )
    (net (code "144") (name "unconnected-(J11-Pad35)") (class "Default")
      (node (ref "J11") (pin "35") (pinfunction "35_35") (pintype "passive+no_connect"))
    )
    (net (code "145") (name "unconnected-(J11-Pad37)") (class "Default")
      (node (ref "J11") (pin "37") (pinfunction "37_37") (pintype "passive+no_connect"))
    )
    (net (code "146") (name "unconnected-(J11-Pad38)") (class "Default")
      (node (ref "J11") (pin "38") (pinfunction "38_38") (pintype "passive+no_connect"))
    )
    (net (code "147") (name "unconnected-(J11-Pad39)") (class "Default")
      (node (ref "J11") (pin "39") (pinfunction "39_39") (pintype "passive+no_connect"))
    )
    (net (code "148") (name "unconnected-(J11-Pad40)") (class "Default")
      (node (ref "J11") (pin "40") (pinfunction "40_40") (pintype "passive+no_connect"))
    )
    (net (code "149") (name "unconnected-(J11-Pad41)") (class "Default")
      (node (ref "J11") (pin "41") (pinfunction "41_41") (pintype "passive+no_connect"))
    )
    (net (code "150") (name "unconnected-(J11-Pad43)") (class "Default")
      (node (ref "J11") (pin "43") (pinfunction "43_43") (pintype "passive+no_connect"))
    )
    (net (code "151") (name "unconnected-(J11-Pad45)") (class "Default")
      (node (ref "J11") (pin "45") (pinfunction "45_45") (pintype "passive+no_connect"))
    )
    (net (code "152") (name "unconnected-(J11-Pad47)") (class "Default")
      (node (ref "J11") (pin "47") (pinfunction "47_47") (pintype "passive+no_connect"))
    )
    (net (code "153") (name "unconnected-(J11-Pad49)") (class "Default")
      (node (ref "J11") (pin "49") (pinfunction "49_49") (pintype "passive+no_connect"))
    )
    (net (code "154") (name "unconnected-(RA2-Pad1)") (class "Default")
      (node (ref "RA2") (pin "1") (pinfunction "1_1") (pintype "passive+no_connect"))
    )
    (net (code "155") (name "unconnected-(RA2-Pad8)") (class "Default")
      (node (ref "RA2") (pin "8") (pinfunction "8_8") (pintype "passive+no_connect"))
    )
    (net (code "156") (name "unconnected-(RA5-Pad4)") (class "Default")
      (node (ref "RA5") (pin "4") (pinfunction "4_4") (pintype "passive+no_connect"))
    )
    (net (code "157") (name "unconnected-(RA5-Pad5)") (class "Default")
      (node (ref "RA5") (pin "5") (pinfunction "5_5") (pintype "passive+no_connect"))
    )
  )
)
